# DFPlayer-Wemos.net
KiCad netlist of a schematic drawn in EAGLE
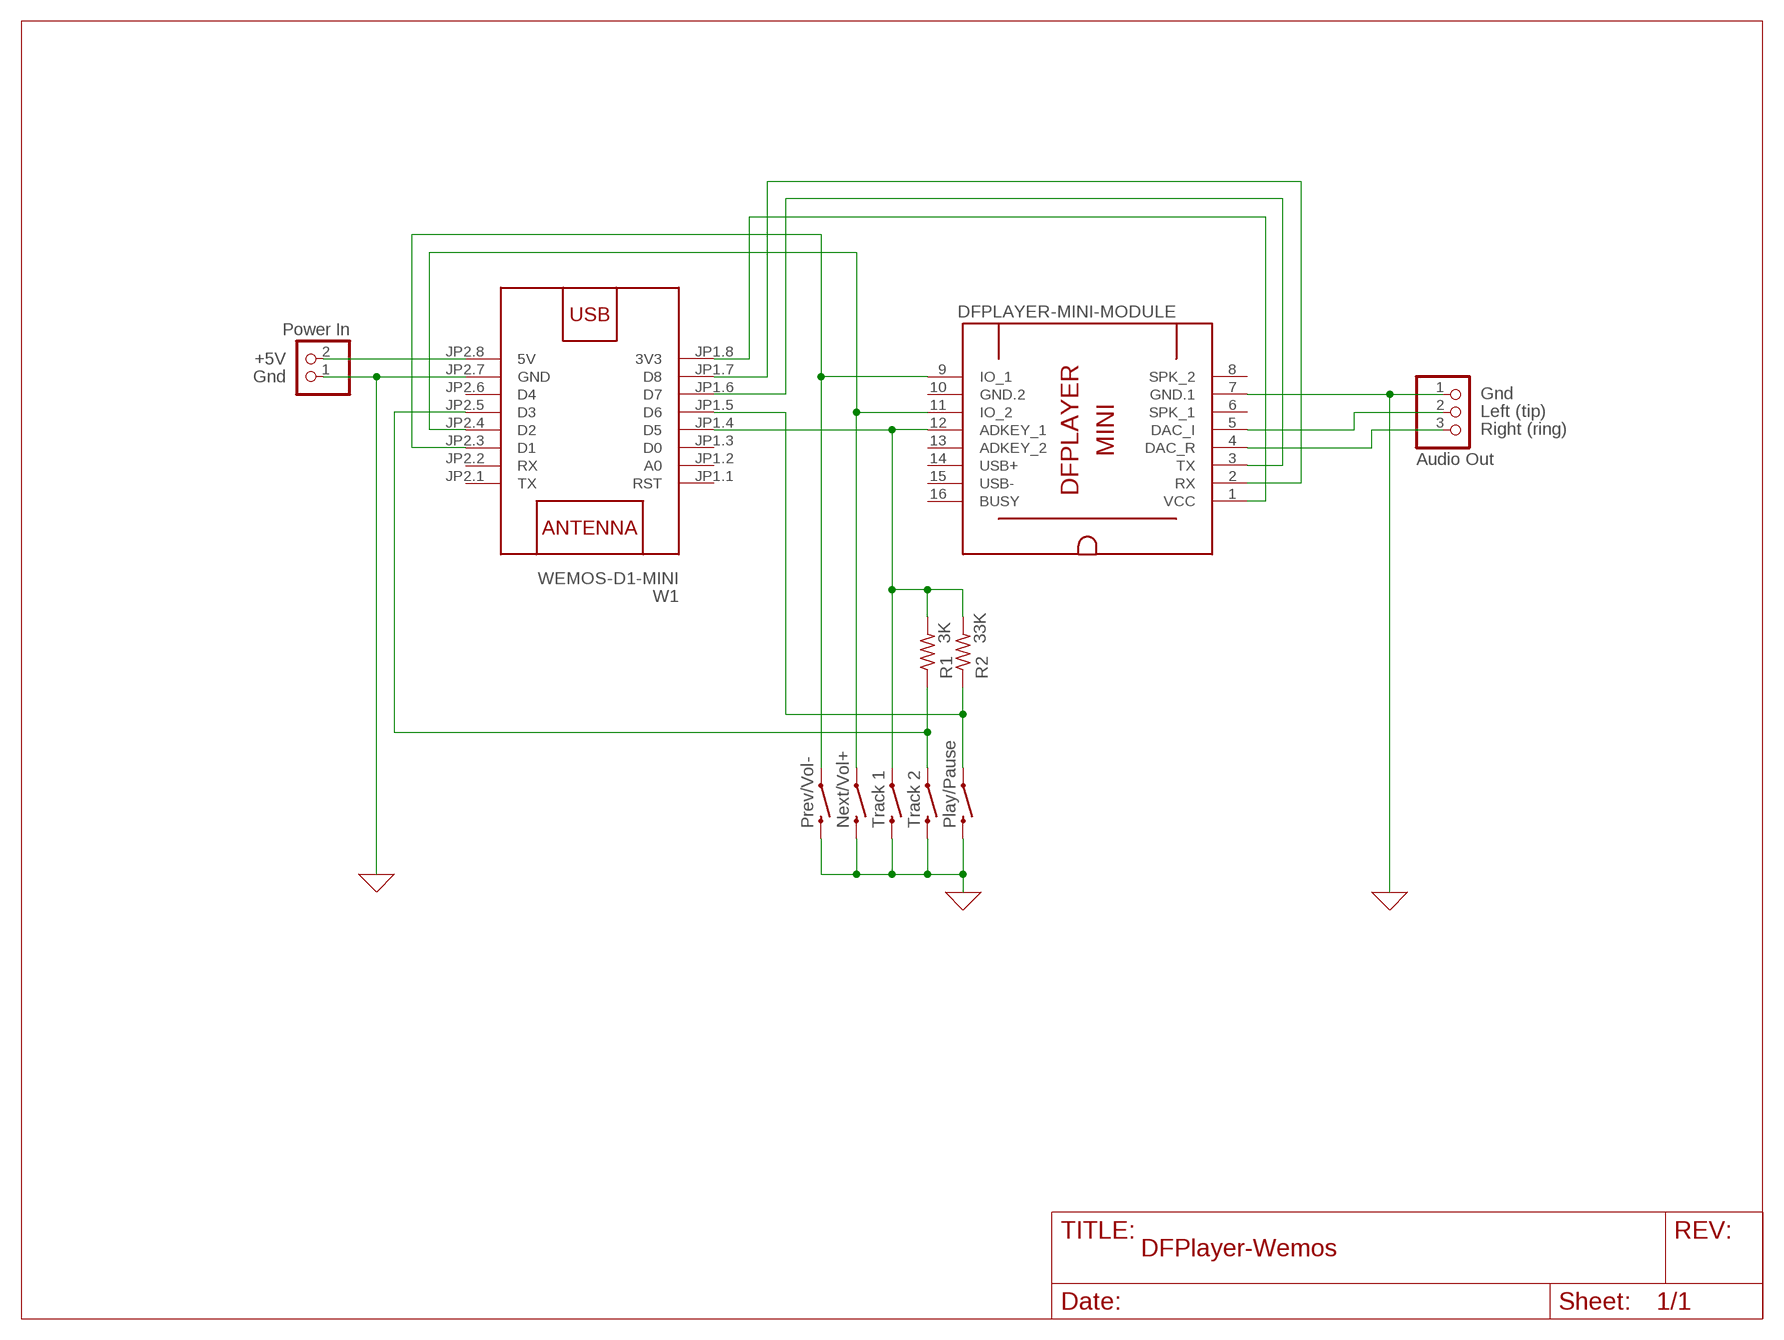
[diagram p0: schematic, sheet 1]

(export (version "E")
  (design (tool "Eeschema 10.0.6"))
  (components
    (comp (ref "JP2")
      (value "Audio Out")
      (footprint "eagle-import:1X03")
      (libsource (lib "eagle-import") (part "PINHD-1X3"))
    )
    (comp (ref "JP3")
      (value "Power In")
      (footprint "eagle-import:1X02")
      (libsource (lib "eagle-import") (part "PINHD-1X2"))
    )
    (comp (ref "R1")
      (value "3K")
      (footprint "eagle-import:0207_10")
      (libsource (lib "eagle-import") (part "R-US_0207/10"))
    )
    (comp (ref "R2")
      (value "33K")
      (footprint "eagle-import:0207_10")
      (libsource (lib "eagle-import") (part "R-US_0207/10"))
    )
    (comp (ref "S2")
      (value "MOMENTARY-SWITCH-SPST-PTH-6.0MM")
      (footprint "eagle-import:TACTILE_SWITCH_PTH_6.0MM")
      (libsource (lib "eagle-import") (part "MOMENTARY-SWITCH-SPST-PTH-6.0MM"))
    )
    (comp (ref "S3")
      (value "MOMENTARY-SWITCH-SPST-PTH-6.0MM")
      (footprint "eagle-import:TACTILE_SWITCH_PTH_6.0MM")
      (libsource (lib "eagle-import") (part "MOMENTARY-SWITCH-SPST-PTH-6.0MM"))
    )
    (comp (ref "S4")
      (value "MOMENTARY-SWITCH-SPST-PTH-6.0MM")
      (footprint "eagle-import:TACTILE_SWITCH_PTH_6.0MM")
      (libsource (lib "eagle-import") (part "MOMENTARY-SWITCH-SPST-PTH-6.0MM"))
    )
    (comp (ref "S5")
      (value "MOMENTARY-SWITCH-SPST-PTH-6.0MM")
      (footprint "eagle-import:TACTILE_SWITCH_PTH_6.0MM")
      (libsource (lib "eagle-import") (part "MOMENTARY-SWITCH-SPST-PTH-6.0MM"))
    )
    (comp (ref "S6")
      (value "MOMENTARY-SWITCH-SPST-PTH-6.0MM")
      (footprint "eagle-import:TACTILE_SWITCH_PTH_6.0MM")
      (libsource (lib "eagle-import") (part "MOMENTARY-SWITCH-SPST-PTH-6.0MM"))
    )
    (comp (ref "U$1")
      (value "DFPLAYER-MINI-MODULE")
      (footprint "eagle-import:DFPLAYER-MINI-MODULE")
      (libsource (lib "eagle-import") (part "DFPLAYER-MINI-MODULE"))
    )
    (comp (ref "W1")
      (value "WEMOS-D1-MINI")
      (footprint "eagle-import:WEMOS-D1-MINI")
      (libsource (lib "eagle-import") (part "WEMOS-D1-MINI"))
    )
  )
  (nets
    (net (code "1") (name "/GND.2") (class "Default")
      (node (ref "U$1") (pin "10") (pinfunction "GND.2_10") (pintype "power_in"))
    )
    (net (code "2") (name "GND") (class "Default")
      (node (ref "JP2") (pin "1") (pinfunction "1_1") (pintype "passive"))
      (node (ref "JP3") (pin "1") (pinfunction "1_1") (pintype "passive"))
      (node (ref "S2") (pin "3") (pinfunction "2_3") (pintype "passive"))
      (node (ref "S3") (pin "3") (pinfunction "2_3") (pintype "passive"))
      (node (ref "S4") (pin "3") (pinfunction "2_3") (pintype "passive"))
      (node (ref "S5") (pin "3") (pinfunction "2_3") (pintype "passive"))
      (node (ref "S6") (pin "3") (pinfunction "2_3") (pintype "passive"))
      (node (ref "U$1") (pin "7") (pinfunction "GND.1_7") (pintype "power_in"))
      (node (ref "W1") (pin "JP2.7") (pinfunction "GND_JP2.7") (pintype "power_in"))
    )
    (net (code "3") (name "Net-(U$1-ADKEY_1)") (class "Default")
      (node (ref "R1") (pin "2") (pinfunction "2_2") (pintype "passive"))
      (node (ref "R2") (pin "2") (pinfunction "2_2") (pintype "passive"))
      (node (ref "S4") (pin "1") (pinfunction "1_1") (pintype "passive"))
      (node (ref "U$1") (pin "12") (pinfunction "ADKEY_1_12") (pintype "bidirectional"))
      (node (ref "W1") (pin "JP1.4") (pinfunction "D5_JP1.4") (pintype "bidirectional"))
    )
    (net (code "4") (name "Net-(U$1-DAC_I)") (class "Default")
      (node (ref "JP2") (pin "2") (pinfunction "2_2") (pintype "passive"))
      (node (ref "U$1") (pin "5") (pinfunction "DAC_I_5") (pintype "bidirectional"))
    )
    (net (code "5") (name "Net-(U$1-DAC_R)") (class "Default")
      (node (ref "JP2") (pin "3") (pinfunction "3_3") (pintype "passive"))
      (node (ref "U$1") (pin "4") (pinfunction "DAC_R_4") (pintype "bidirectional"))
    )
    (net (code "6") (name "Net-(U$1-IO_1)") (class "Default")
      (node (ref "S3") (pin "1") (pinfunction "1_1") (pintype "passive"))
      (node (ref "U$1") (pin "9") (pinfunction "IO_1_9") (pintype "bidirectional"))
      (node (ref "W1") (pin "JP2.3") (pinfunction "D1_JP2.3") (pintype "bidirectional"))
    )
    (net (code "7") (name "Net-(U$1-IO_2)") (class "Default")
      (node (ref "S2") (pin "1") (pinfunction "1_1") (pintype "passive"))
      (node (ref "U$1") (pin "11") (pinfunction "IO_2_11") (pintype "bidirectional"))
      (node (ref "W1") (pin "JP2.4") (pinfunction "D2_JP2.4") (pintype "bidirectional"))
    )
    (net (code "8") (name "Net-(U$1-RX)") (class "Default")
      (node (ref "U$1") (pin "2") (pinfunction "RX_2") (pintype "bidirectional"))
      (node (ref "W1") (pin "JP1.7") (pinfunction "D8_JP1.7") (pintype "bidirectional"))
    )
    (net (code "9") (name "Net-(U$1-TX)") (class "Default")
      (node (ref "U$1") (pin "3") (pinfunction "TX_3") (pintype "bidirectional"))
      (node (ref "W1") (pin "JP1.6") (pinfunction "D7_JP1.6") (pintype "bidirectional"))
    )
    (net (code "10") (name "Net-(U$1-VCC)") (class "Default")
      (node (ref "U$1") (pin "1") (pinfunction "VCC_1") (pintype "power_in"))
      (node (ref "W1") (pin "JP1.8") (pinfunction "3V3_JP1.8") (pintype "power_in"))
    )
    (net (code "11") (name "Net-(W1-5V)") (class "Default")
      (node (ref "JP3") (pin "2") (pinfunction "2_2") (pintype "passive"))
      (node (ref "W1") (pin "JP2.8") (pinfunction "5V_JP2.8") (pintype "power_in"))
    )
    (net (code "12") (name "Net-(W1-D3)") (class "Default")
      (node (ref "R1") (pin "1") (pinfunction "1_1") (pintype "passive"))
      (node (ref "S6") (pin "1") (pinfunction "1_1") (pintype "passive"))
      (node (ref "W1") (pin "JP2.5") (pinfunction "D3_JP2.5") (pintype "bidirectional"))
    )
    (net (code "13") (name "Net-(W1-D6)") (class "Default")
      (node (ref "R2") (pin "1") (pinfunction "1_1") (pintype "passive"))
      (node (ref "S5") (pin "1") (pinfunction "1_1") (pintype "passive"))
      (node (ref "W1") (pin "JP1.5") (pinfunction "D6_JP1.5") (pintype "bidirectional"))
    )
    (net (code "14") (name "unconnected-(U$1-ADKEY_2-Pad13)") (class "Default")
      (node (ref "U$1") (pin "13") (pinfunction "ADKEY_2_13") (pintype "bidirectional"))
    )
    (net (code "15") (name "unconnected-(U$1-BUSY-Pad16)") (class "Default")
      (node (ref "U$1") (pin "16") (pinfunction "BUSY_16") (pintype "bidirectional"))
    )
    (net (code "16") (name "unconnected-(U$1-SPK_1-Pad6)") (class "Default")
      (node (ref "U$1") (pin "6") (pinfunction "SPK_1_6") (pintype "bidirectional"))
    )
    (net (code "17") (name "unconnected-(U$1-SPK_2-Pad8)") (class "Default")
      (node (ref "U$1") (pin "8") (pinfunction "SPK_2_8") (pintype "bidirectional"))
    )
    (net (code "18") (name "unconnected-(U$1-USB+-Pad14)") (class "Default")
      (node (ref "U$1") (pin "14") (pinfunction "USB+_14") (pintype "bidirectional"))
    )
    (net (code "19") (name "unconnected-(U$1-USB--Pad15)") (class "Default")
      (node (ref "U$1") (pin "15") (pinfunction "USB-_15") (pintype "bidirectional"))
    )
    (net (code "20") (name "unconnected-(W1-A0-PadJP1.2)") (class "Default")
      (node (ref "W1") (pin "JP1.2") (pinfunction "A0_JP1.2") (pintype "bidirectional"))
    )
    (net (code "21") (name "unconnected-(W1-D0-PadJP1.3)") (class "Default")
      (node (ref "W1") (pin "JP1.3") (pinfunction "D0_JP1.3") (pintype "bidirectional"))
    )
    (net (code "22") (name "unconnected-(W1-D4-PadJP2.6)") (class "Default")
      (node (ref "W1") (pin "JP2.6") (pinfunction "D4_JP2.6") (pintype "bidirectional"))
    )
    (net (code "23") (name "unconnected-(W1-RST-PadJP1.1)") (class "Default")
      (node (ref "W1") (pin "JP1.1") (pinfunction "RST_JP1.1") (pintype "bidirectional"))
    )
    (net (code "24") (name "unconnected-(W1-RX-PadJP2.2)") (class "Default")
      (node (ref "W1") (pin "JP2.2") (pinfunction "RX_JP2.2") (pintype "bidirectional"))
    )
    (net (code "25") (name "unconnected-(W1-TX-PadJP2.1)") (class "Default")
      (node (ref "W1") (pin "JP2.1") (pinfunction "TX_JP2.1") (pintype "bidirectional"))
    )
  )
)
